# ProProject_minifoc_test_4_0_2024-05-25.net
KiCad netlist of a schematic drawn in EasyEDA Pro
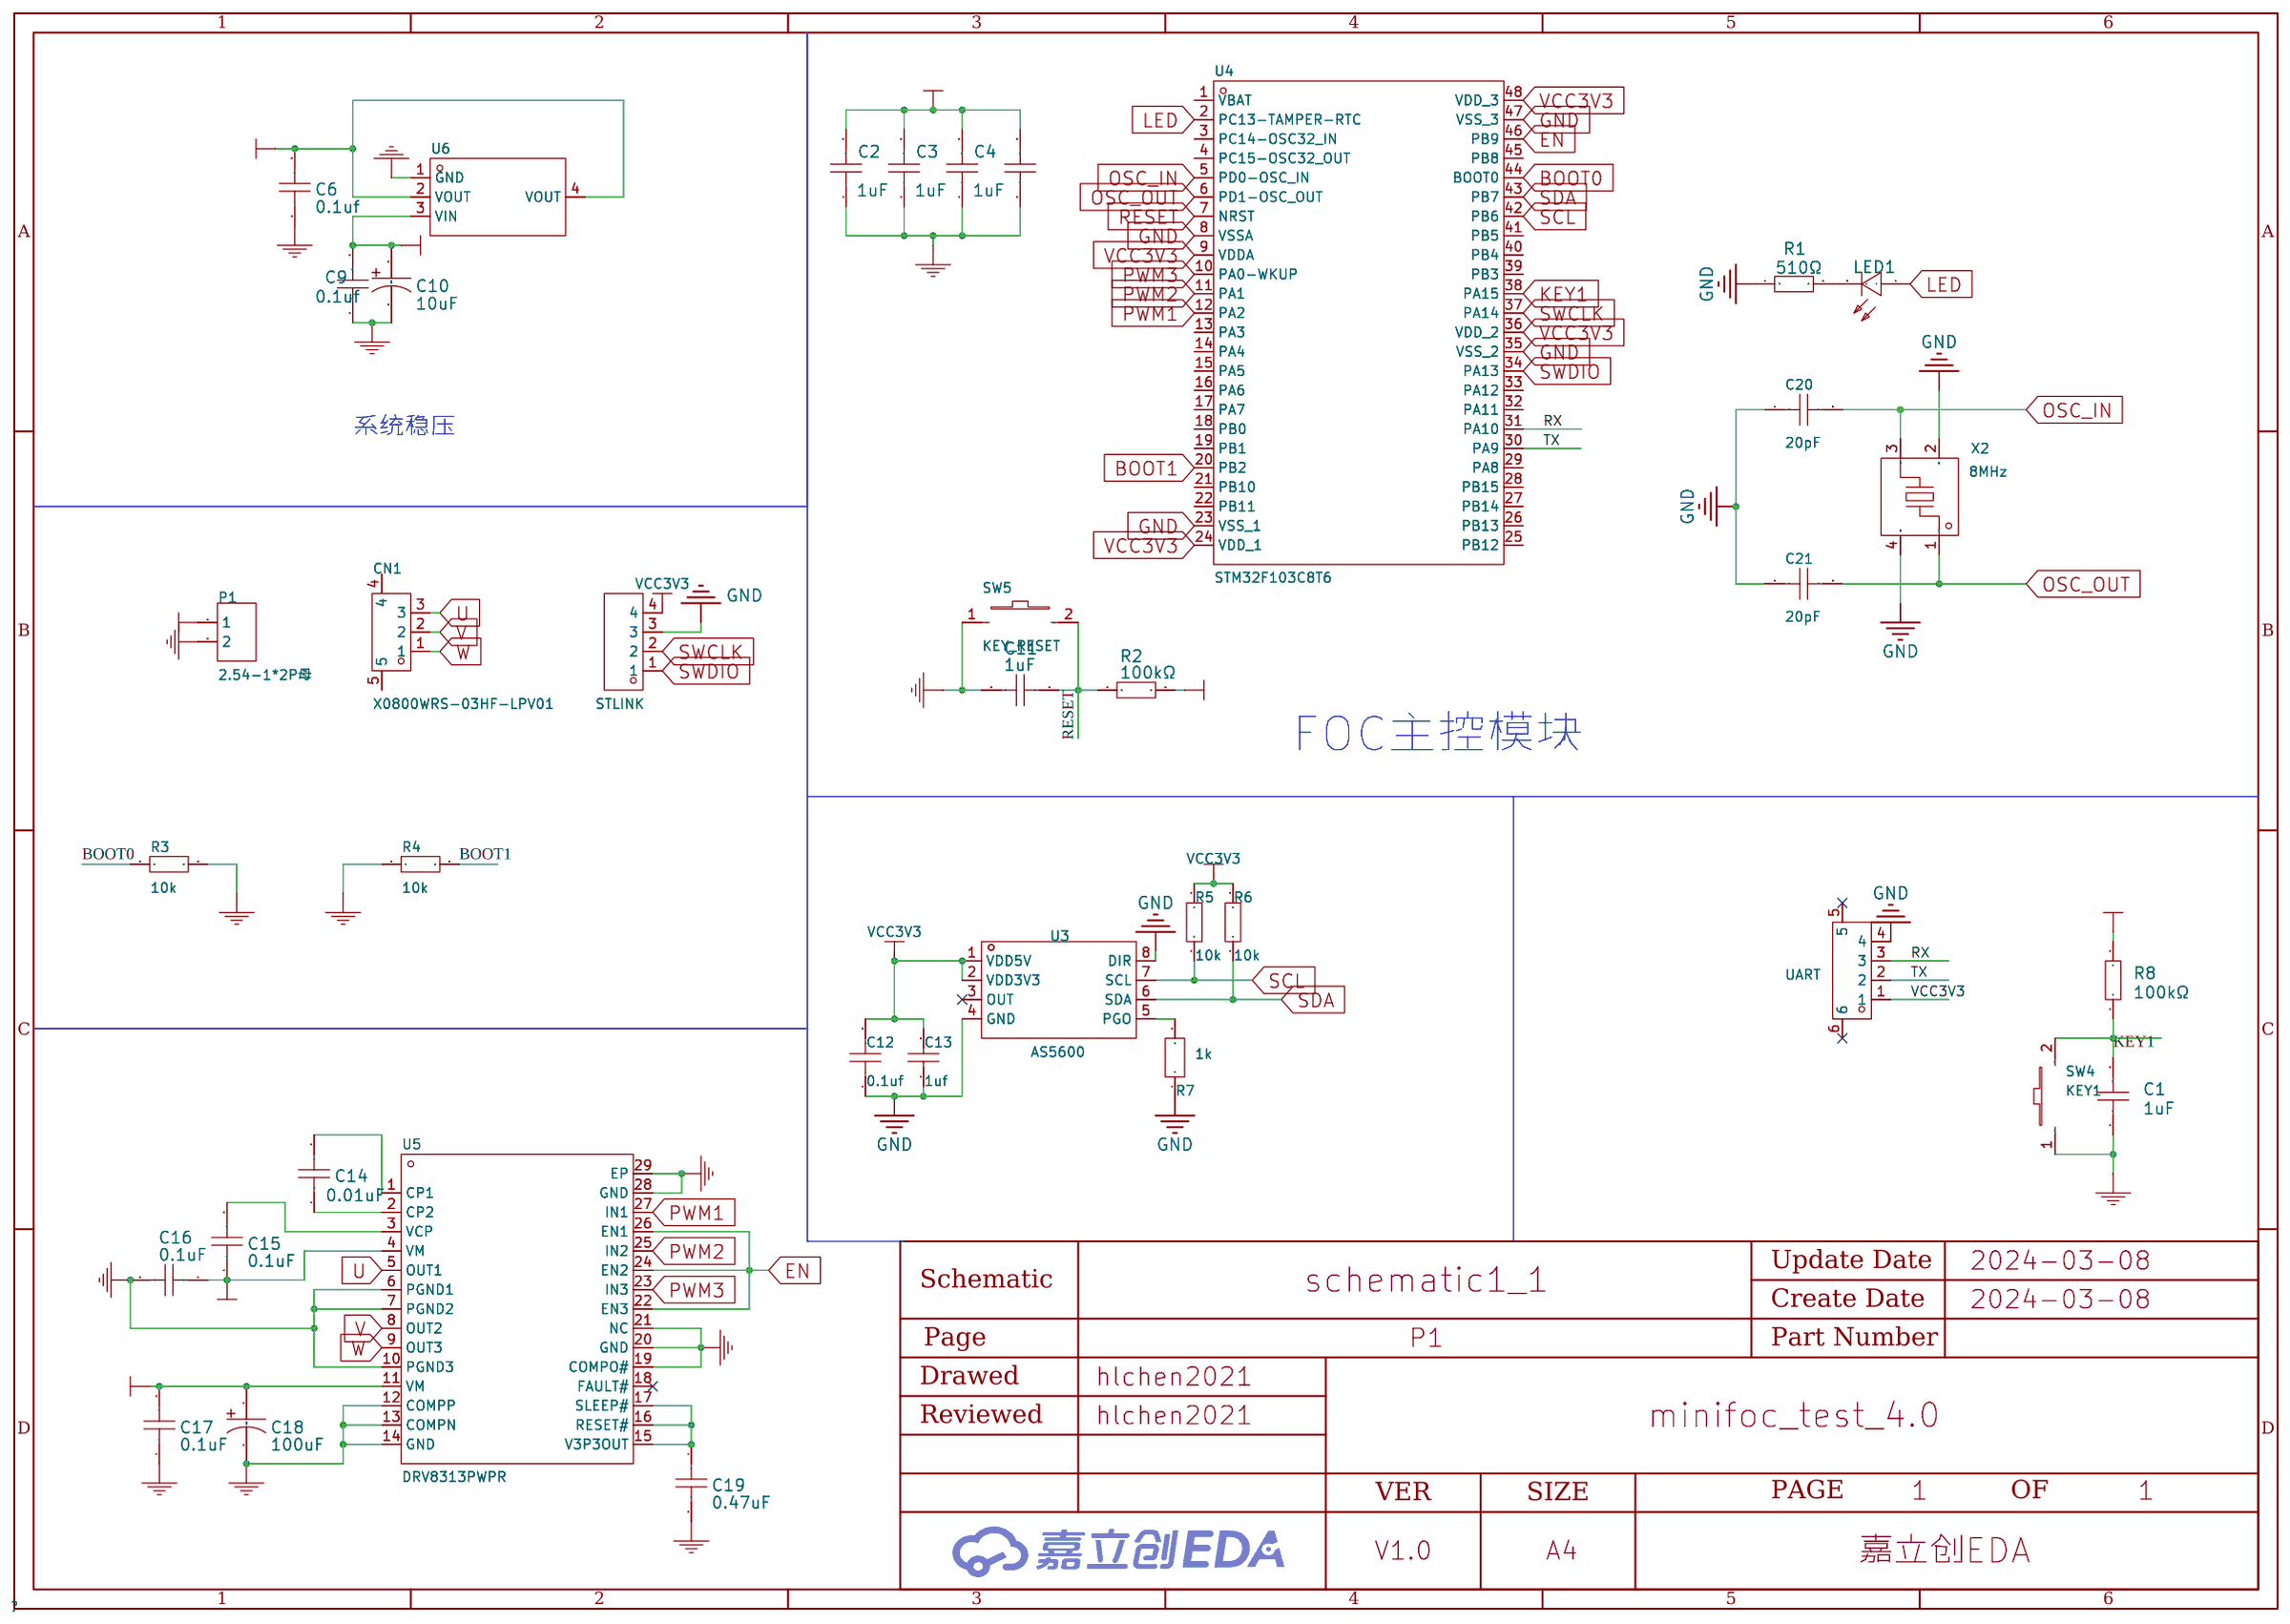
[diagram p0: schematic sheet]

(export (version "E")
  (design (tool "Eeschema 10.0.6"))
  (components
    (comp (ref "C1")
      (value "1uF")
      (footprint "easyedapro:C0603")
      (fields
        (field (name "Manufacturer Part") "0603F105M160NT")
        (field (name "Manufacturer") "FH(风华)")
        (field (name "Tolerance") "±20%")
      )
      (libsource (lib "easyedapro") (part "1uF"))
    )
    (comp (ref "C2")
      (value "1uF")
      (footprint "easyedapro:C0603")
      (fields
        (field (name "Manufacturer Part") "0603F105M160NT")
        (field (name "Manufacturer") "FH(风华)")
        (field (name "Tolerance") "±20%")
      )
      (libsource (lib "easyedapro") (part "1uF"))
    )
    (comp (ref "C3")
      (value "1uF")
      (footprint "easyedapro:C0603")
      (fields
        (field (name "Manufacturer Part") "0603F105M160NT")
        (field (name "Manufacturer") "FH(风华)")
        (field (name "Tolerance") "±20%")
      )
      (libsource (lib "easyedapro") (part "1uF"))
    )
    (comp (ref "C4")
      (value "1uF")
      (footprint "easyedapro:C0603")
      (fields
        (field (name "Manufacturer Part") "0603F105M160NT")
        (field (name "Manufacturer") "FH(风华)")
        (field (name "Tolerance") "±20%")
      )
      (libsource (lib "easyedapro") (part "1uF"))
    )
    (comp (ref "C5")
      (value "1uF")
      (footprint "easyedapro:C0603")
      (fields
        (field (name "Manufacturer Part") "0603F105M160NT")
        (field (name "Manufacturer") "FH(风华)")
        (field (name "Tolerance") "±20%")
      )
      (libsource (lib "easyedapro") (part "1uF"))
    )
    (comp (ref "C6")
      (value "0.1uf")
      (footprint "easyedapro:C0603")
      (libsource (lib "easyedapro") (part "0.1uf"))
    )
    (comp (ref "C9")
      (value "0.1uf")
      (footprint "easyedapro:C0603")
      (libsource (lib "easyedapro") (part "0.1uf"))
    )
    (comp (ref "C10")
      (value "10uF")
      (footprint "easyedapro:CAP-SMD_L3.2-W1.6-RD")
      (fields (field (name "Manufacturer Part") "TC212A106M010A") (field (name "Manufacturer") "Sunlord"))
      (libsource (lib "easyedapro") (part "10uF"))
    )
    (comp (ref "C11")
      (value "1uF")
      (footprint "easyedapro:C0603")
      (fields
        (field (name "Manufacturer Part") "0603F105M160NT")
        (field (name "Manufacturer") "FH(风华)")
        (field (name "Tolerance") "±20%")
      )
      (libsource (lib "easyedapro") (part "1uF"))
    )
    (comp (ref "C12")
      (value "100nF")
      (footprint "easyedapro:C0603")
      (description "容值:100nF;精度:±10%;额定电压:50V;材质(温度系数):X7R;")
      (fields
        (field (name "Manufacturer Part") "CC0603KRX7R9BB104")
        (field (name "Manufacturer") "YAGEO(国巨)")
      )
      (libsource (lib "easyedapro") (part "CC0603KRX7R9BB104"))
    )
    (comp (ref "C13")
      (value "1uF")
      (footprint "easyedapro:C0603")
      (description "容值:1uF;精度:±20%;额定电压:16V;材质(温度系数):Y5V;")
      (fields (field (name "Manufacturer Part") "0603F105M160NT") (field (name "Manufacturer") "FH(风华)"))
      (libsource (lib "easyedapro") (part "0603F105M160NT"))
    )
    (comp (ref "C14")
      (value "0.01uF")
      (footprint "easyedapro:C0603")
      (libsource (lib "easyedapro") (part "0.01uF"))
    )
    (comp (ref "C15")
      (value "0.1uF")
      (footprint "easyedapro:C0603")
      (libsource (lib "easyedapro") (part "0.1uf"))
    )
    (comp (ref "C16")
      (value "0.1uF")
      (footprint "easyedapro:C0603")
      (libsource (lib "easyedapro") (part "0.1uf"))
    )
    (comp (ref "C17")
      (value "0.1uF")
      (footprint "easyedapro:C0603")
      (libsource (lib "easyedapro") (part "0.1uf"))
    )
    (comp (ref "C18")
      (value "100uF")
      (fields (field (name "Manufacturer Part") "CA45-C-10V-100μF-K") (field (name "Manufacturer") "TORCH"))
      (libsource (lib "easyedapro") (part "100uF"))
    )
    (comp (ref "C19")
      (value "0.47uF")
      (footprint "easyedapro:C0603")
      (libsource (lib "easyedapro") (part "0.47uF"))
    )
    (comp (ref "C20")
      (value "20pF")
      (footprint "easyedapro:C0603")
      (description "容值:20pF;精度:±5%;额定电压:100V;材质(温度系数):C0G;额定电压(VAC):-;")
      (fields (field (name "Manufacturer Part") "0603CG200J101NT") (field (name "Manufacturer") "FH(风华)"))
      (libsource (lib "easyedapro") (part "0603CG200J101NT"))
    )
    (comp (ref "C21")
      (value "20pF")
      (footprint "easyedapro:C0603")
      (description "容值:20pF;精度:±5%;额定电压:100V;材质(温度系数):C0G;额定电压(VAC):-;")
      (fields (field (name "Manufacturer Part") "0603CG200J101NT") (field (name "Manufacturer") "FH(风华)"))
      (libsource (lib "easyedapro") (part "0603CG200J101NT"))
    )
    (comp (ref "CN1")
      (value "X0800WRS-03HF-LPV01")
      (footprint "easyedapro:CONN-SMD_X0800WRS-03HF-LPV01")
      (fields (field (name "Manufacturer") "XKB Connectivity(中国星坤)"))
      (libsource (lib "easyedapro") (part "X0800WRS-03HF-LPV01"))
    )
    (comp (ref "LED1")
      (value "FC-DA1608HRK-620D")
      (footprint "easyedapro:LED0603-FD")
      (fields (field (name "Manufacturer") "NATIONSTAR"))
      (libsource (lib "easyedapro") (part "FC-DA1608HRK-620D"))
    )
    (comp (ref "P1")
      (value "2.54-1*2P母")
      (footprint "easyedapro:HDR-TH_2P-P2.54-V-F")
      (description "排数:单排;总孔位数:2P;间距:2.54mm;插孔结构:1x2P;行距:-;安装类型:直插;塑高:-;触头材质:-;触头镀层:-;")
      (fields (field (name "Manufacturer") "BOOMELE(博穆精密)"))
      (libsource (lib "easyedapro") (part "Header-Female-2.54_1x2"))
    )
    (comp (ref "R1")
      (value "510Ω")
      (footprint "easyedapro:R0603")
      (fields (field (name "Manufacturer Part") "RS-03K511JT") (field (name "Manufacturer") "FH"))
      (libsource (lib "easyedapro") (part "510Ω"))
    )
    (comp (ref "R2")
      (value "100kΩ")
      (footprint "easyedapro:R0603")
      (fields
        (field (name "Manufacturer Part") "HoLTT0603-1/10W-100KR-1%")
        (field (name "Manufacturer") "Milliohm(毫欧)")
      )
      (libsource (lib "easyedapro") (part "100k"))
    )
    (comp (ref "R3")
      (value "10kΩ")
      (footprint "easyedapro:R0603")
      (description "电阻类型:厚膜电阻;阻值:10kΩ;精度:±1%;功率:100mW;温度系数:±100ppm/;最大工作电压:75V;工作温度范围:-55~+155;")
      (fields
        (field (name "Manufacturer Part") "0603WAF1002T5E")
        (field (name "Manufacturer") "UNI-ROYAL(厚声)")
      )
      (libsource (lib "easyedapro") (part "0603WAF1002T5E"))
    )
    (comp (ref "R4")
      (value "10kΩ")
      (footprint "easyedapro:R0603")
      (description "电阻类型:厚膜电阻;阻值:10kΩ;精度:±1%;功率:100mW;温度系数:±100ppm/;最大工作电压:75V;工作温度范围:-55~+155;")
      (fields
        (field (name "Manufacturer Part") "0603WAF1002T5E")
        (field (name "Manufacturer") "UNI-ROYAL(厚声)")
      )
      (libsource (lib "easyedapro") (part "0603WAF1002T5E"))
    )
    (comp (ref "R5")
      (value "10kΩ")
      (footprint "easyedapro:R0603")
      (description "电阻类型:厚膜电阻;阻值:10kΩ;精度:±1%;功率:100mW;温度系数:±100ppm/;最大工作电压:75V;工作温度范围:-55~+155;")
      (fields
        (field (name "Manufacturer Part") "0603WAF1002T5E")
        (field (name "Manufacturer") "UNI-ROYAL(厚声)")
      )
      (libsource (lib "easyedapro") (part "0603WAF1002T5E"))
    )
    (comp (ref "R6")
      (value "10kΩ")
      (footprint "easyedapro:R0603")
      (description "电阻类型:厚膜电阻;阻值:10kΩ;精度:±1%;功率:100mW;温度系数:±100ppm/;最大工作电压:75V;工作温度范围:-55~+155;")
      (fields
        (field (name "Manufacturer Part") "0603WAF1002T5E")
        (field (name "Manufacturer") "UNI-ROYAL(厚声)")
      )
      (libsource (lib "easyedapro") (part "0603WAF1002T5E"))
    )
    (comp (ref "R7")
      (value "1k")
      (footprint "easyedapro:R0603")
      (fields (field (name "Manufacturer Part") "SCR0603J1K") (field (name "Manufacturer") "VO(翔胜)"))
      (libsource (lib "easyedapro") (part "SCR0603J1K"))
    )
    (comp (ref "R8")
      (value "100kΩ")
      (footprint "easyedapro:R0603")
      (fields
        (field (name "Manufacturer Part") "HoLTT0603-1/10W-100KR-1%")
        (field (name "Manufacturer") "Milliohm(毫欧)")
      )
      (libsource (lib "easyedapro") (part "100k"))
    )
    (comp (ref "STLINK")
      (value "2.54-1*4P反弯排针")
      (footprint "easyedapro:HDR-TH_4P-P2.54-H-M-W10.4")
      (fields (field (name "Manufacturer") "BOOMELE(博穆精密)"))
      (libsource (lib "easyedapro") (part "2.54-1*4P反弯排针"))
    )
    (comp (ref "SW4")
      (value "KEY1")
      (footprint "easyedapro:SW-SMD_L4.0-W2.9-LS5.0")
      (libsource (lib "easyedapro") (part "KEY-3*4*2"))
    )
    (comp (ref "SW5")
      (value "KEY_RESET")
      (footprint "easyedapro:SW-SMD_L4.0-W2.9-LS5.0")
      (libsource (lib "easyedapro") (part "KEY-3*4*2"))
    )
    (comp (ref "U3")
      (value "AS5600")
      (footprint "easyedapro:SOIC-8_L5.0-W4.0-P1.27-LS6.0-BL")
      (description "非接触12bit磁角度位置传感器")
      (fields (field (name "Manufacturer Part") "AS5600-ASOM") (field (name "Manufacturer") "ams(艾迈斯半导体)"))
      (libsource (lib "easyedapro") (part "AS5600-ASOM"))
    )
    (comp (ref "U4")
      (value "STM32F103C8T6")
      (footprint "easyedapro:LQFP-48_L7.0-W7.0-P0.50-LS9.0-BL")
      (fields (field (name "Manufacturer") "ST(意法半导体)"))
      (libsource (lib "easyedapro") (part "STM32F103C8T6"))
    )
    (comp (ref "U5")
      (value "DRV8313PWPR")
      (footprint "easyedapro:HTSSOP-28_L9.8-W4.5-P0.65-LS6.6-BL-EP")
      (description "DRV8313 三路 1/2 H 桥驱动器 IC")
      (fields (field (name "Manufacturer") "TI(德州仪器)"))
      (libsource (lib "easyedapro") (part "DRV8313PWPR"))
    )
    (comp (ref "U6")
      (value "AMS1117-3.3")
      (footprint "easyedapro:SOT-223-3_L6.5-W3.4-P2.30-LS7.0-BR")
      (fields (field (name "Manufacturer") "美国AMS"))
      (libsource (lib "easyedapro") (part "AMS1117-3.3"))
    )
    (comp (ref "UART")
      (value "HDGC1002WR-S-4P")
      (footprint "easyedapro:CONN-SMD_4P-P1.00_HDGC_HDGC1002WR-S-4P")
      (description "参考系列:-;间距:1mm;插针结构:1x4P;排数:1;每排PIN数:4;行距:-;公母:公型插针;安装方式:卧贴;额定电流:1A;工作温度范围:-25~+70;")
      (fields (field (name "Manufacturer") "HDGC(华德共创)"))
      (libsource (lib "easyedapro") (part "HDGC1002WR-S-4P"))
    )
    (comp (ref "X2")
      (value "8MHz")
      (footprint "easyedapro:OSC-SMD_4P-L3.2-W2.5-BL")
      (description "晶振类型:贴片无源晶振;频率:8MHz;频率公差:±10ppm;频率稳定度:-;负载电容:10pF;工作温度:-;")
      (fields
        (field (name "Manufacturer Part") "3225-8.00-10-10-10/A")
        (field (name "Manufacturer") "LIMING(利明)")
      )
      (libsource (lib "easyedapro") (part "3225-8.00-10-10-10/A"))
    )
  )
  (nets
    (net (code "1") (name "/RX") (class "Default")
      (node (ref "U4") (pin "31") (pinfunction "PA10_31") (pintype "input"))
      (node (ref "UART") (pin "3") (pinfunction "3_3") (pintype "input"))
    )
    (net (code "2") (name "/TX") (class "Default")
      (node (ref "U4") (pin "30") (pinfunction "PA9_30") (pintype "input"))
      (node (ref "UART") (pin "2") (pinfunction "2_2") (pintype "input"))
    )
    (net (code "3") (name "BOOT0") (class "Default")
      (node (ref "R3") (pin "1") (pinfunction "1_1") (pintype "input"))
      (node (ref "U4") (pin "44") (pinfunction "BOOT0_44") (pintype "input"))
    )
    (net (code "4") (name "BOOT1") (class "Default")
      (node (ref "R4") (pin "2") (pinfunction "2_2") (pintype "input"))
      (node (ref "U4") (pin "20") (pinfunction "PB2_20") (pintype "input"))
    )
    (net (code "5") (name "EN") (class "Default")
      (node (ref "U4") (pin "46") (pinfunction "PB9_46") (pintype "input"))
      (node (ref "U5") (pin "22") (pinfunction "EN3_22") (pintype "input"))
      (node (ref "U5") (pin "24") (pinfunction "EN2_24") (pintype "input"))
      (node (ref "U5") (pin "26") (pinfunction "EN1_26") (pintype "input"))
    )
    (net (code "6") (name "GND") (class "Default")
      (node (ref "C1") (pin "1") (pinfunction "1_1") (pintype "input"))
      (node (ref "C10") (pin "2") (pinfunction "2_2") (pintype "input"))
      (node (ref "C11") (pin "1") (pinfunction "1_1") (pintype "input"))
      (node (ref "C12") (pin "1") (pinfunction "1_1") (pintype "input"))
      (node (ref "C13") (pin "1") (pinfunction "1_1") (pintype "input"))
      (node (ref "C16") (pin "2") (pinfunction "2_2") (pintype "input"))
      (node (ref "C17") (pin "1") (pinfunction "1_1") (pintype "input"))
      (node (ref "C18") (pin "2") (pinfunction "2_2") (pintype "input"))
      (node (ref "C19") (pin "2") (pinfunction "2_2") (pintype "input"))
      (node (ref "C2") (pin "1") (pinfunction "1_1") (pintype "input"))
      (node (ref "C20") (pin "1") (pinfunction "1_1") (pintype "input"))
      (node (ref "C21") (pin "1") (pinfunction "1_1") (pintype "input"))
      (node (ref "C3") (pin "1") (pinfunction "1_1") (pintype "input"))
      (node (ref "C4") (pin "1") (pinfunction "1_1") (pintype "input"))
      (node (ref "C5") (pin "1") (pinfunction "1_1") (pintype "input"))
      (node (ref "C6") (pin "1") (pinfunction "1_1") (pintype "input"))
      (node (ref "C9") (pin "1") (pinfunction "1_1") (pintype "input"))
      (node (ref "P1") (pin "2") (pinfunction "2_2") (pintype "input"))
      (node (ref "R1") (pin "1") (pinfunction "1_1") (pintype "input"))
      (node (ref "R3") (pin "2") (pinfunction "2_2") (pintype "input"))
      (node (ref "R4") (pin "1") (pinfunction "1_1") (pintype "input"))
      (node (ref "R7") (pin "1") (pinfunction "1_1") (pintype "input"))
      (node (ref "STLINK") (pin "3") (pinfunction "3_3") (pintype "input"))
      (node (ref "SW4") (pin "1") (pinfunction "1_1") (pintype "input"))
      (node (ref "SW5") (pin "1") (pinfunction "1_1") (pintype "input"))
      (node (ref "U3") (pin "4") (pinfunction "GND_4") (pintype "input"))
      (node (ref "U3") (pin "8") (pinfunction "DIR_8") (pintype "input"))
      (node (ref "U4") (pin "23") (pinfunction "VSS_1_23") (pintype "input"))
      (node (ref "U4") (pin "35") (pinfunction "VSS_2_35") (pintype "input"))
      (node (ref "U4") (pin "47") (pinfunction "VSS_3_47") (pintype "input"))
      (node (ref "U4") (pin "8") (pinfunction "VSSA_8") (pintype "input"))
      (node (ref "U5") (pin "10") (pinfunction "PGND3_10") (pintype "input"))
      (node (ref "U5") (pin "12") (pinfunction "COMPP_12") (pintype "input"))
      (node (ref "U5") (pin "13") (pinfunction "COMPN_13") (pintype "input"))
      (node (ref "U5") (pin "14") (pinfunction "GND_14") (pintype "input"))
      (node (ref "U5") (pin "19") (pinfunction "COMPO#_19") (pintype "input"))
      (node (ref "U5") (pin "20") (pinfunction "GND_20") (pintype "input"))
      (node (ref "U5") (pin "21") (pinfunction "NC_21") (pintype "input"))
      (node (ref "U5") (pin "28") (pinfunction "GND_28") (pintype "input"))
      (node (ref "U5") (pin "29") (pinfunction "EP_29") (pintype "input"))
      (node (ref "U5") (pin "6") (pinfunction "PGND1_6") (pintype "input"))
      (node (ref "U5") (pin "7") (pinfunction "PGND2_7") (pintype "input"))
      (node (ref "U6") (pin "1") (pinfunction "GND_1") (pintype "input"))
      (node (ref "UART") (pin "4") (pinfunction "4_4") (pintype "input"))
      (node (ref "X2") (pin "2") (pinfunction "GND_2") (pintype "input"))
      (node (ref "X2") (pin "4") (pinfunction "GND_4") (pintype "input"))
    )
    (net (code "7") (name "KEY1") (class "Default")
      (node (ref "C1") (pin "2") (pinfunction "2_2") (pintype "input"))
      (node (ref "R8") (pin "1") (pinfunction "1_1") (pintype "input"))
      (node (ref "SW4") (pin "2") (pinfunction "2_2") (pintype "input"))
      (node (ref "U4") (pin "38") (pinfunction "PA15_38") (pintype "input"))
    )
    (net (code "8") (name "LED") (class "Default")
      (node (ref "LED1") (pin "1") (pinfunction "A_1") (pintype "input"))
      (node (ref "U4") (pin "2") (pinfunction "PC13-TAMPER-RTC_2") (pintype "input"))
    )
    (net (code "9") (name "Net-(LED1-K)") (class "Default")
      (node (ref "LED1") (pin "2") (pinfunction "K_2") (pintype "input"))
      (node (ref "R1") (pin "2") (pinfunction "2_2") (pintype "input"))
    )
    (net (code "10") (name "Net-(U3-PGO)") (class "Default")
      (node (ref "R7") (pin "2") (pinfunction "2_2") (pintype "input"))
      (node (ref "U3") (pin "5") (pinfunction "PGO_5") (pintype "input"))
    )
    (net (code "11") (name "Net-(U5-CP1)") (class "Default")
      (node (ref "C14") (pin "2") (pinfunction "2_2") (pintype "input"))
      (node (ref "U5") (pin "1") (pinfunction "CP1_1") (pintype "input"))
    )
    (net (code "12") (name "Net-(U5-CP2)") (class "Default")
      (node (ref "C14") (pin "1") (pinfunction "1_1") (pintype "input"))
      (node (ref "U5") (pin "2") (pinfunction "CP2_2") (pintype "input"))
    )
    (net (code "13") (name "Net-(U5-RESET#)") (class "Default")
      (node (ref "C19") (pin "1") (pinfunction "1_1") (pintype "input"))
      (node (ref "U5") (pin "15") (pinfunction "V3P3OUT_15") (pintype "input"))
      (node (ref "U5") (pin "16") (pinfunction "RESET#_16") (pintype "input"))
      (node (ref "U5") (pin "17") (pinfunction "SLEEP#_17") (pintype "input"))
    )
    (net (code "14") (name "Net-(U5-VCP)") (class "Default")
      (node (ref "C15") (pin "2") (pinfunction "2_2") (pintype "input"))
      (node (ref "U5") (pin "3") (pinfunction "VCP_3") (pintype "input"))
    )
    (net (code "15") (name "OSC_IN") (class "Default")
      (node (ref "C20") (pin "2") (pinfunction "2_2") (pintype "input"))
      (node (ref "U4") (pin "5") (pinfunction "PD0-OSC_IN_5") (pintype "input"))
      (node (ref "X2") (pin "3") (pinfunction "3_3") (pintype "input"))
    )
    (net (code "16") (name "OSC_OUT") (class "Default")
      (node (ref "C21") (pin "2") (pinfunction "2_2") (pintype "input"))
      (node (ref "U4") (pin "6") (pinfunction "PD1-OSC_OUT_6") (pintype "input"))
      (node (ref "X2") (pin "1") (pinfunction "1_1") (pintype "input"))
    )
    (net (code "17") (name "PWM1") (class "Default")
      (node (ref "U4") (pin "12") (pinfunction "PA2_12") (pintype "input"))
      (node (ref "U5") (pin "27") (pinfunction "IN1_27") (pintype "input"))
    )
    (net (code "18") (name "PWM2") (class "Default")
      (node (ref "U4") (pin "11") (pinfunction "PA1_11") (pintype "input"))
      (node (ref "U5") (pin "25") (pinfunction "IN2_25") (pintype "input"))
    )
    (net (code "19") (name "PWM3") (class "Default")
      (node (ref "U4") (pin "10") (pinfunction "PA0-WKUP_10") (pintype "input"))
      (node (ref "U5") (pin "23") (pinfunction "IN3_23") (pintype "input"))
    )
    (net (code "20") (name "RESET") (class "Default")
      (node (ref "C11") (pin "2") (pinfunction "2_2") (pintype "input"))
      (node (ref "R2") (pin "1") (pinfunction "1_1") (pintype "input"))
      (node (ref "SW5") (pin "2") (pinfunction "2_2") (pintype "input"))
      (node (ref "U4") (pin "7") (pinfunction "NRST_7") (pintype "input"))
    )
    (net (code "21") (name "SCL") (class "Default")
      (node (ref "R5") (pin "1") (pinfunction "1_1") (pintype "input"))
      (node (ref "U3") (pin "7") (pinfunction "SCL_7") (pintype "input"))
      (node (ref "U4") (pin "42") (pinfunction "PB6_42") (pintype "input"))
    )
    (net (code "22") (name "SDA") (class "Default")
      (node (ref "R6") (pin "1") (pinfunction "1_1") (pintype "input"))
      (node (ref "U3") (pin "6") (pinfunction "SDA_6") (pintype "input"))
      (node (ref "U4") (pin "43") (pinfunction "PB7_43") (pintype "input"))
    )
    (net (code "23") (name "SWCLK") (class "Default")
      (node (ref "STLINK") (pin "2") (pinfunction "2_2") (pintype "input"))
      (node (ref "U4") (pin "37") (pinfunction "PA14_37") (pintype "input"))
    )
    (net (code "24") (name "SWDIO") (class "Default")
      (node (ref "STLINK") (pin "1") (pinfunction "1_1") (pintype "input"))
      (node (ref "U4") (pin "34") (pinfunction "PA13_34") (pintype "input"))
    )
    (net (code "25") (name "U") (class "Default")
      (node (ref "CN1") (pin "3") (pinfunction "3_3") (pintype "unspecified"))
      (node (ref "U5") (pin "5") (pinfunction "OUT1_5") (pintype "input"))
    )
    (net (code "26") (name "V") (class "Default")
      (node (ref "CN1") (pin "2") (pinfunction "2_2") (pintype "unspecified"))
      (node (ref "U5") (pin "8") (pinfunction "OUT2_8") (pintype "input"))
    )
    (net (code "27") (name "VCC") (class "Default")
      (node (ref "C10") (pin "1") (pinfunction "1_1") (pintype "input"))
      (node (ref "C15") (pin "1") (pinfunction "1_1") (pintype "input"))
      (node (ref "C16") (pin "1") (pinfunction "1_1") (pintype "input"))
      (node (ref "C17") (pin "2") (pinfunction "2_2") (pintype "input"))
      (node (ref "C18") (pin "1") (pinfunction "1_1") (pintype "input"))
      (node (ref "C9") (pin "2") (pinfunction "2_2") (pintype "input"))
      (node (ref "P1") (pin "1") (pinfunction "1_1") (pintype "input"))
      (node (ref "U5") (pin "11") (pinfunction "VM_11") (pintype "input"))
      (node (ref "U5") (pin "4") (pinfunction "VM_4") (pintype "input"))
      (node (ref "U6") (pin "3") (pinfunction "VIN_3") (pintype "input"))
    )
    (net (code "28") (name "VCC3V3") (class "Default")
      (node (ref "C12") (pin "2") (pinfunction "2_2") (pintype "input"))
      (node (ref "C13") (pin "2") (pinfunction "2_2") (pintype "input"))
      (node (ref "C2") (pin "2") (pinfunction "2_2") (pintype "input"))
      (node (ref "C3") (pin "2") (pinfunction "2_2") (pintype "input"))
      (node (ref "C4") (pin "2") (pinfunction "2_2") (pintype "input"))
      (node (ref "C5") (pin "2") (pinfunction "2_2") (pintype "input"))
      (node (ref "C6") (pin "2") (pinfunction "2_2") (pintype "input"))
      (node (ref "R2") (pin "2") (pinfunction "2_2") (pintype "input"))
      (node (ref "R5") (pin "2") (pinfunction "2_2") (pintype "input"))
      (node (ref "R6") (pin "2") (pinfunction "2_2") (pintype "input"))
      (node (ref "R8") (pin "2") (pinfunction "2_2") (pintype "input"))
      (node (ref "STLINK") (pin "4") (pinfunction "4_4") (pintype "input"))
      (node (ref "U3") (pin "1") (pinfunction "VDD5V_1") (pintype "input"))
      (node (ref "U3") (pin "2") (pinfunction "VDD3V3_2") (pintype "input"))
      (node (ref "U4") (pin "24") (pinfunction "VDD_1_24") (pintype "input"))
      (node (ref "U4") (pin "36") (pinfunction "VDD_2_36") (pintype "input"))
      (node (ref "U4") (pin "48") (pinfunction "VDD_3_48") (pintype "input"))
      (node (ref "U4") (pin "9") (pinfunction "VDDA_9") (pintype "input"))
      (node (ref "U6") (pin "2") (pinfunction "VOUT_2") (pintype "input"))
      (node (ref "U6") (pin "4") (pinfunction "VOUT_4") (pintype "input"))
      (node (ref "UART") (pin "1") (pinfunction "1_1") (pintype "input"))
    )
    (net (code "29") (name "W") (class "Default")
      (node (ref "CN1") (pin "1") (pinfunction "1_1") (pintype "unspecified"))
      (node (ref "U5") (pin "9") (pinfunction "OUT3_9") (pintype "input"))
    )
    (net (code "30") (name "unconnected-(CN1-Pad4)") (class "Default")
      (node (ref "CN1") (pin "4") (pinfunction "4_4") (pintype "unspecified"))
    )
    (net (code "31") (name "unconnected-(CN1-Pad5)") (class "Default")
      (node (ref "CN1") (pin "5") (pinfunction "5_5") (pintype "unspecified"))
    )
    (net (code "32") (name "unconnected-(U3-OUT-Pad3)") (class "Default")
      (node (ref "U3") (pin "3") (pinfunction "OUT_3") (pintype "input+no_connect"))
    )
    (net (code "33") (name "unconnected-(U4-PA3-Pad13)") (class "Default")
      (node (ref "U4") (pin "13") (pinfunction "PA3_13") (pintype "input"))
    )
    (net (code "34") (name "unconnected-(U4-PA4-Pad14)") (class "Default")
      (node (ref "U4") (pin "14") (pinfunction "PA4_14") (pintype "input"))
    )
    (net (code "35") (name "unconnected-(U4-PA5-Pad15)") (class "Default")
      (node (ref "U4") (pin "15") (pinfunction "PA5_15") (pintype "input"))
    )
    (net (code "36") (name "unconnected-(U4-PA6-Pad16)") (class "Default")
      (node (ref "U4") (pin "16") (pinfunction "PA6_16") (pintype "input"))
    )
    (net (code "37") (name "unconnected-(U4-PA7-Pad17)") (class "Default")
      (node (ref "U4") (pin "17") (pinfunction "PA7_17") (pintype "input"))
    )
    (net (code "38") (name "unconnected-(U4-PA8-Pad29)") (class "Default")
      (node (ref "U4") (pin "29") (pinfunction "PA8_29") (pintype "input"))
    )
    (net (code "39") (name "unconnected-(U4-PA11-Pad32)") (class "Default")
      (node (ref "U4") (pin "32") (pinfunction "PA11_32") (pintype "input"))
    )
    (net (code "40") (name "unconnected-(U4-PA12-Pad33)") (class "Default")
      (node (ref "U4") (pin "33") (pinfunction "PA12_33") (pintype "input"))
    )
    (net (code "41") (name "unconnected-(U4-PB0-Pad18)") (class "Default")
      (node (ref "U4") (pin "18") (pinfunction "PB0_18") (pintype "input"))
    )
    (net (code "42") (name "unconnected-(U4-PB1-Pad19)") (class "Default")
      (node (ref "U4") (pin "19") (pinfunction "PB1_19") (pintype "input"))
    )
    (net (code "43") (name "unconnected-(U4-PB3-Pad39)") (class "Default")
      (node (ref "U4") (pin "39") (pinfunction "PB3_39") (pintype "input"))
    )
    (net (code "44") (name "unconnected-(U4-PB4-Pad40)") (class "Default")
      (node (ref "U4") (pin "40") (pinfunction "PB4_40") (pintype "input"))
    )
    (net (code "45") (name "unconnected-(U4-PB5-Pad41)") (class "Default")
      (node (ref "U4") (pin "41") (pinfunction "PB5_41") (pintype "input"))
    )
    (net (code "46") (name "unconnected-(U4-PB8-Pad45)") (class "Default")
      (node (ref "U4") (pin "45") (pinfunction "PB8_45") (pintype "input"))
    )
    (net (code "47") (name "unconnected-(U4-PB10-Pad21)") (class "Default")
      (node (ref "U4") (pin "21") (pinfunction "PB10_21") (pintype "input"))
    )
    (net (code "48") (name "unconnected-(U4-PB11-Pad22)") (class "Default")
      (node (ref "U4") (pin "22") (pinfunction "PB11_22") (pintype "input"))
    )
    (net (code "49") (name "unconnected-(U4-PB12-Pad25)") (class "Default")
      (node (ref "U4") (pin "25") (pinfunction "PB12_25") (pintype "input"))
    )
    (net (code "50") (name "unconnected-(U4-PB13-Pad26)") (class "Default")
      (node (ref "U4") (pin "26") (pinfunction "PB13_26") (pintype "input"))
    )
    (net (code "51") (name "unconnected-(U4-PB14-Pad27)") (class "Default")
      (node (ref "U4") (pin "27") (pinfunction "PB14_27") (pintype "input"))
    )
    (net (code "52") (name "unconnected-(U4-PB15-Pad28)") (class "Default")
      (node (ref "U4") (pin "28") (pinfunction "PB15_28") (pintype "input"))
    )
    (net (code "53") (name "unconnected-(U4-PC14-OSC32_IN-Pad3)") (class "Default")
      (node (ref "U4") (pin "3") (pinfunction "PC14-OSC32_IN_3") (pintype "input"))
    )
    (net (code "54") (name "unconnected-(U4-PC15-OSC32_OUT-Pad4)") (class "Default")
      (node (ref "U4") (pin "4") (pinfunction "PC15-OSC32_OUT_4") (pintype "input"))
    )
    (net (code "55") (name "unconnected-(U4-VBAT-Pad1)") (class "Default")
      (node (ref "U4") (pin "1") (pinfunction "VBAT_1") (pintype "input"))
    )
    (net (code "56") (name "unconnected-(U5-FAULT#-Pad18)") (class "Default")
      (node (ref "U5") (pin "18") (pinfunction "FAULT#_18") (pintype "input+no_connect"))
    )
    (net (code "57") (name "unconnected-(UART-Pad5)") (class "Default")
      (node (ref "UART") (pin "5") (pinfunction "5_5") (pintype "input+no_connect"))
    )
    (net (code "58") (name "unconnected-(UART-Pad6)") (class "Default")
      (node (ref "UART") (pin "6") (pinfunction "6_6") (pintype "input+no_connect"))
    )
  )
)
